# 5V_Voltage_Regulator_For_Servos.net
KiCad netlist of a schematic drawn in EAGLE
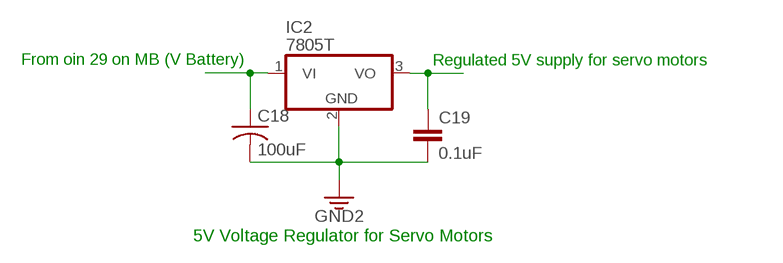
[diagram p0: schematic, sheet 1]

(export (version "E")
  (design (tool "Eeschema 10.0.6"))
  (components
    (comp (ref "C18")
      (value "100uF")
      (footprint "eagle-import:C025-024X044")
      (libsource (lib "eagle-import") (part "C-US025-024X044"))
    )
    (comp (ref "C19")
      (value "0.1uF")
      (footprint "eagle-import:1206")
      (libsource (lib "eagle-import") (part "2.2UF-CERCAP-10009"))
    )
    (comp (ref "IC2")
      (value "7805T")
      (footprint "eagle-import:TO220H")
      (libsource (lib "eagle-import") (part "78T05"))
    )
  )
  (nets
    (net (code "1") (name "GND2") (class "Default")
      (node (ref "C18") (pin "2") (pinfunction "2_2") (pintype "passive"))
      (node (ref "C19") (pin "2") (pinfunction "2_2") (pintype "passive"))
      (node (ref "IC2") (pin "2") (pinfunction "GND_2") (pintype "passive"))
    )
    (net (code "2") (name "Net-(IC2-VI)") (class "Default")
      (node (ref "C18") (pin "1") (pinfunction "1_1") (pintype "passive"))
      (node (ref "IC2") (pin "1") (pinfunction "VI_1") (pintype "input"))
    )
    (net (code "3") (name "Net-(IC2-VO)") (class "Default")
      (node (ref "C19") (pin "1") (pinfunction "1_1") (pintype "passive"))
      (node (ref "IC2") (pin "3") (pinfunction "VO_3") (pintype "passive"))
    )
  )
)
